# tuya-jailbeaker.net
KiCad netlist of a schematic drawn in EAGLE
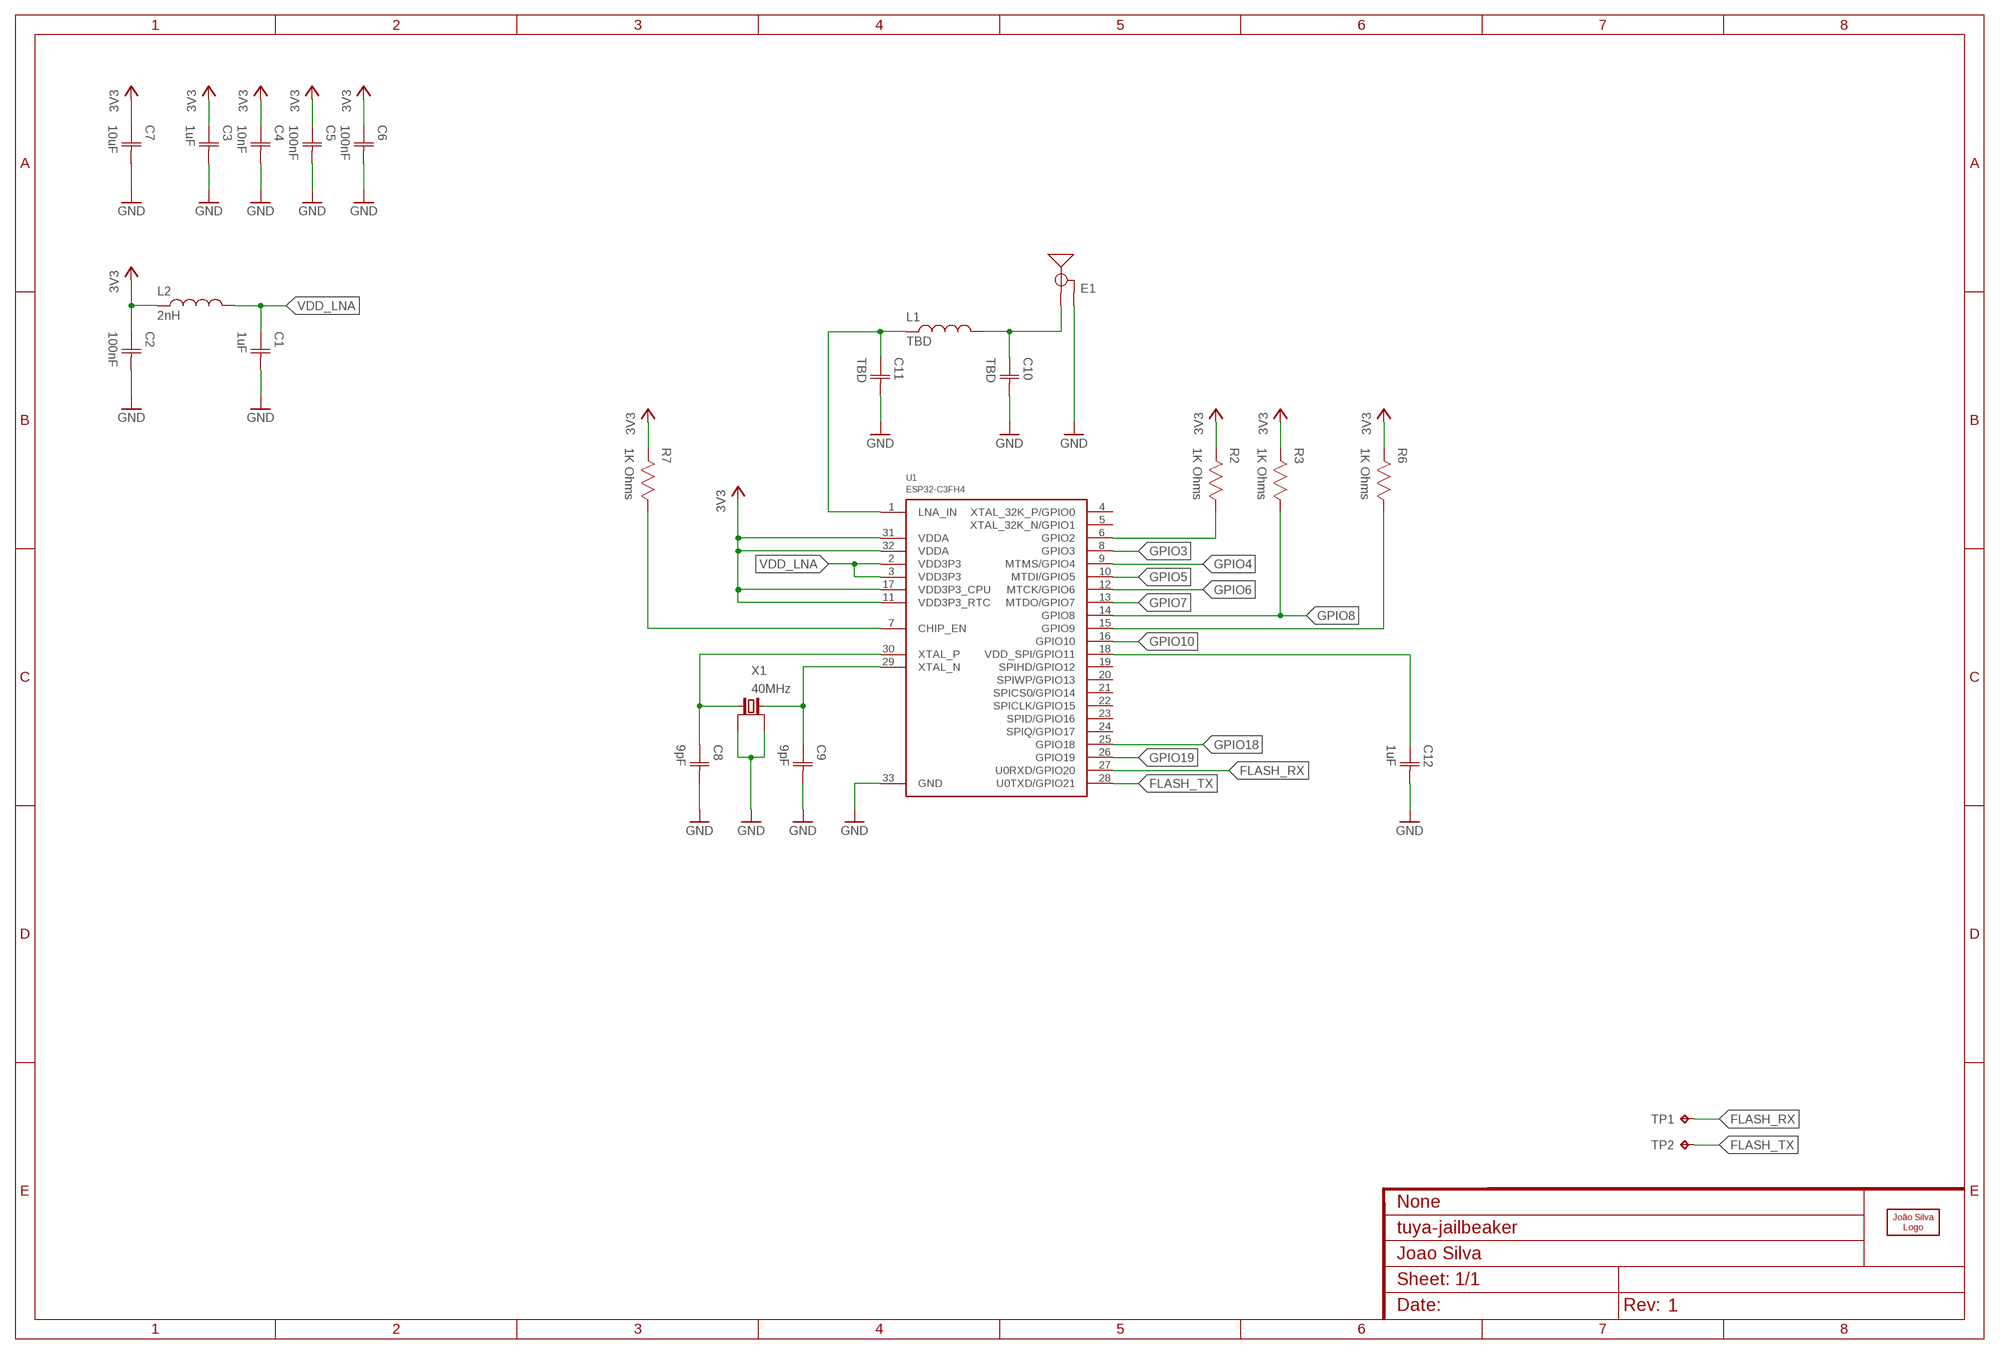
[diagram p0: schematic, sheet 1]

(export (version "E")
  (design (tool "Eeschema 10.0.6"))
  (components
    (comp (ref "C1")
      (value "1uF")
      (footprint "eagle-import:CAP0402")
      (libsource (lib "eagle-import") (part "CAPACITOR-0402"))
    )
    (comp (ref "C2")
      (value "100nF")
      (footprint "eagle-import:CAP0402")
      (libsource (lib "eagle-import") (part "CAPACITOR-0402"))
    )
    (comp (ref "C3")
      (value "1uF")
      (footprint "eagle-import:CAP0402")
      (libsource (lib "eagle-import") (part "CAPACITOR-0402"))
    )
    (comp (ref "C4")
      (value "10nF")
      (footprint "eagle-import:CAP0402")
      (libsource (lib "eagle-import") (part "CAPACITOR-0402"))
    )
    (comp (ref "C5")
      (value "100nF")
      (footprint "eagle-import:CAP0402")
      (libsource (lib "eagle-import") (part "CAPACITOR-0402"))
    )
    (comp (ref "C6")
      (value "100nF")
      (footprint "eagle-import:CAP0402")
      (libsource (lib "eagle-import") (part "CAPACITOR-0402"))
    )
    (comp (ref "C7")
      (value "10uF")
      (footprint "eagle-import:CAP0603")
      (libsource (lib "eagle-import") (part "CAPACITOR-0603"))
    )
    (comp (ref "C8")
      (value "9pF")
      (footprint "eagle-import:CAP0402")
      (libsource (lib "eagle-import") (part "CAPACITOR-0402"))
    )
    (comp (ref "C9")
      (value "9pF")
      (footprint "eagle-import:CAP0402")
      (libsource (lib "eagle-import") (part "CAPACITOR-0402"))
    )
    (comp (ref "C10")
      (value "TBD")
      (footprint "eagle-import:CAP0402")
      (libsource (lib "eagle-import") (part "CAPACITOR-0402"))
    )
    (comp (ref "C11")
      (value "TBD")
      (footprint "eagle-import:CAP0402")
      (libsource (lib "eagle-import") (part "CAPACITOR-0402"))
    )
    (comp (ref "C12")
      (value "1uF")
      (footprint "eagle-import:CAP0402")
      (libsource (lib "eagle-import") (part "CAPACITOR-0402"))
    )
    (comp (ref "E1")
      (value "2.4GHZ")
      (footprint "eagle-import:OLIMEX_ANT_ESP8266_ANT")
      (libsource (lib "eagle-import") (part "2.4GHZ"))
    )
    (comp (ref "L1")
      (value "TBD")
      (footprint "eagle-import:IND0402")
      (libsource (lib "eagle-import") (part "INDUCTOR-0402"))
    )
    (comp (ref "L2")
      (value "2nH")
      (footprint "eagle-import:IND0402")
      (libsource (lib "eagle-import") (part "INDUCTOR-0402"))
    )
    (comp (ref "LOGO1")
      (value "JS-5MM")
      (footprint "eagle-import:JS_5MM")
      (libsource (lib "eagle-import") (part "JS-5MM"))
    )
    (comp (ref "R2")
      (value "1K Ohms")
      (footprint "eagle-import:RES0402")
      (libsource (lib "eagle-import") (part "RESISTOR-0402"))
    )
    (comp (ref "R3")
      (value "1K Ohms")
      (footprint "eagle-import:RES0402")
      (libsource (lib "eagle-import") (part "RESISTOR-0402"))
    )
    (comp (ref "R6")
      (value "1K Ohms")
      (footprint "eagle-import:RES0402")
      (libsource (lib "eagle-import") (part "RESISTOR-0402"))
    )
    (comp (ref "R7")
      (value "1K Ohms")
      (footprint "eagle-import:RES0402")
      (libsource (lib "eagle-import") (part "RESISTOR-0402"))
    )
    (comp (ref "TP1")
      (value "TESTPOINT-1.27MM")
      (footprint "eagle-import:PAD1.27MM")
      (libsource (lib "eagle-import") (part "TESTPOINT-1.27MM"))
    )
    (comp (ref "TP2")
      (value "TESTPOINT-1.27MM")
      (footprint "eagle-import:PAD1.27MM")
      (libsource (lib "eagle-import") (part "TESTPOINT-1.27MM"))
    )
    (comp (ref "U1")
      (value "ESP32-C3FH4")
      (footprint "eagle-import:QFN32")
      (libsource (lib "eagle-import") (part "ESP32-C3FH4"))
    )
    (comp (ref "X1")
      (value "40MHz")
      (footprint "eagle-import:4-SMD-2520")
      (libsource (lib "eagle-import") (part "CRYSTAL_4P-2520"))
    )
  )
  (nets
    (net (code "1") (name "3V3") (class "Default")
      (node (ref "C2") (pin "1") (pinfunction "C1_1") (pintype "passive"))
      (node (ref "C3") (pin "1") (pinfunction "C1_1") (pintype "passive"))
      (node (ref "C4") (pin "1") (pinfunction "C1_1") (pintype "passive"))
      (node (ref "C5") (pin "1") (pinfunction "C1_1") (pintype "passive"))
      (node (ref "C6") (pin "1") (pinfunction "C1_1") (pintype "passive"))
      (node (ref "C7") (pin "1") (pinfunction "C1_1") (pintype "passive"))
      (node (ref "L2") (pin "1") (pinfunction "1_1") (pintype "passive"))
      (node (ref "R2") (pin "2") (pinfunction "2_2") (pintype "passive"))
      (node (ref "R3") (pin "2") (pinfunction "2_2") (pintype "passive"))
      (node (ref "R6") (pin "2") (pinfunction "2_2") (pintype "passive"))
      (node (ref "R7") (pin "2") (pinfunction "2_2") (pintype "passive"))
      (node (ref "U1") (pin "11") (pinfunction "VDD3P3_RTC_11") (pintype "bidirectional"))
      (node (ref "U1") (pin "17") (pinfunction "VDD3P3_CPU_17") (pintype "bidirectional"))
      (node (ref "U1") (pin "31") (pinfunction "VDDA_31") (pintype "bidirectional"))
      (node (ref "U1") (pin "32") (pinfunction "VDDA_32") (pintype "bidirectional"))
    )
    (net (code "2") (name "FLASH_RX") (class "Default")
      (node (ref "TP1") (pin "TP") (pinfunction "TP_TP") (pintype "input"))
      (node (ref "U1") (pin "27") (pinfunction "U0RXD/GPIO20_27") (pintype "bidirectional"))
    )
    (net (code "3") (name "FLASH_TX") (class "Default")
      (node (ref "TP2") (pin "TP") (pinfunction "TP_TP") (pintype "input"))
      (node (ref "U1") (pin "28") (pinfunction "U0TXD/GPIO21_28") (pintype "bidirectional"))
    )
    (net (code "4") (name "GND") (class "Default")
      (node (ref "C1") (pin "2") (pinfunction "C2_2") (pintype "passive"))
      (node (ref "C10") (pin "2") (pinfunction "C2_2") (pintype "passive"))
      (node (ref "C11") (pin "2") (pinfunction "C2_2") (pintype "passive"))
      (node (ref "C12") (pin "2") (pinfunction "C2_2") (pintype "passive"))
      (node (ref "C2") (pin "2") (pinfunction "C2_2") (pintype "passive"))
      (node (ref "C3") (pin "2") (pinfunction "C2_2") (pintype "passive"))
      (node (ref "C4") (pin "2") (pinfunction "C2_2") (pintype "passive"))
      (node (ref "C5") (pin "2") (pinfunction "C2_2") (pintype "passive"))
      (node (ref "C6") (pin "2") (pinfunction "C2_2") (pintype "passive"))
      (node (ref "C7") (pin "2") (pinfunction "C2_2") (pintype "passive"))
      (node (ref "C8") (pin "2") (pinfunction "C2_2") (pintype "passive"))
      (node (ref "C9") (pin "2") (pinfunction "C2_2") (pintype "passive"))
      (node (ref "E1") (pin "GND") (pinfunction "GND_GND") (pintype "bidirectional"))
      (node (ref "U1") (pin "33") (pinfunction "GND_33") (pintype "bidirectional"))
      (node (ref "X1") (pin "2") (pinfunction "GND_2") (pintype "passive"))
      (node (ref "X1") (pin "4") (pinfunction "GND_4") (pintype "passive"))
    )
    (net (code "5") (name "GPIO3") (class "Default")
      (node (ref "U1") (pin "8") (pinfunction "GPIO3_8") (pintype "bidirectional"))
    )
    (net (code "6") (name "GPIO4") (class "Default")
      (node (ref "U1") (pin "9") (pinfunction "MTMS/GPIO4_9") (pintype "bidirectional"))
    )
    (net (code "7") (name "GPIO5") (class "Default")
      (node (ref "U1") (pin "10") (pinfunction "MTDI/GPIO5_10") (pintype "bidirectional"))
    )
    (net (code "8") (name "GPIO6") (class "Default")
      (node (ref "U1") (pin "12") (pinfunction "MTCK/GPIO6_12") (pintype "bidirectional"))
    )
    (net (code "9") (name "GPIO7") (class "Default")
      (node (ref "U1") (pin "13") (pinfunction "MTDO/GPIO7_13") (pintype "bidirectional"))
    )
    (net (code "10") (name "GPIO8") (class "Default")
      (node (ref "R3") (pin "1") (pinfunction "1_1") (pintype "passive"))
      (node (ref "U1") (pin "14") (pinfunction "GPIO8_14") (pintype "bidirectional"))
    )
    (net (code "11") (name "GPIO10") (class "Default")
      (node (ref "U1") (pin "16") (pinfunction "GPIO10_16") (pintype "bidirectional"))
    )
    (net (code "12") (name "GPIO18") (class "Default")
      (node (ref "U1") (pin "25") (pinfunction "GPIO18_25") (pintype "bidirectional"))
    )
    (net (code "13") (name "GPIO19") (class "Default")
      (node (ref "U1") (pin "26") (pinfunction "GPIO19_26") (pintype "bidirectional"))
    )
    (net (code "14") (name "Net-(C8-C1)") (class "Default")
      (node (ref "C8") (pin "1") (pinfunction "C1_1") (pintype "passive"))
      (node (ref "U1") (pin "30") (pinfunction "XTAL_P_30") (pintype "bidirectional"))
      (node (ref "X1") (pin "3") (pinfunction "1_3") (pintype "passive"))
    )
    (net (code "15") (name "Net-(C9-C1)") (class "Default")
      (node (ref "C9") (pin "1") (pinfunction "C1_1") (pintype "passive"))
      (node (ref "U1") (pin "29") (pinfunction "XTAL_N_29") (pintype "bidirectional"))
      (node (ref "X1") (pin "1") (pinfunction "2_1") (pintype "passive"))
    )
    (net (code "16") (name "Net-(C10-C1)") (class "Default")
      (node (ref "C10") (pin "1") (pinfunction "C1_1") (pintype "passive"))
      (node (ref "E1") (pin "ANT") (pinfunction "SIGNAL_ANT") (pintype "bidirectional"))
      (node (ref "L1") (pin "2") (pinfunction "2_2") (pintype "passive"))
    )
    (net (code "17") (name "Net-(C11-C1)") (class "Default")
      (node (ref "C11") (pin "1") (pinfunction "C1_1") (pintype "passive"))
      (node (ref "L1") (pin "1") (pinfunction "1_1") (pintype "passive"))
      (node (ref "U1") (pin "1") (pinfunction "LNA_IN_1") (pintype "bidirectional"))
    )
    (net (code "18") (name "Net-(C12-C1)") (class "Default")
      (node (ref "C12") (pin "1") (pinfunction "C1_1") (pintype "passive"))
      (node (ref "U1") (pin "18") (pinfunction "VDD_SPI/GPIO11_18") (pintype "bidirectional"))
    )
    (net (code "19") (name "Net-(U1-CHIP_EN)") (class "Default")
      (node (ref "R7") (pin "1") (pinfunction "1_1") (pintype "passive"))
      (node (ref "U1") (pin "7") (pinfunction "CHIP_EN_7") (pintype "bidirectional"))
    )
    (net (code "20") (name "Net-(U1-GPIO2)") (class "Default")
      (node (ref "R2") (pin "1") (pinfunction "1_1") (pintype "passive"))
      (node (ref "U1") (pin "6") (pinfunction "GPIO2_6") (pintype "bidirectional"))
    )
    (net (code "21") (name "Net-(U1-GPIO9)") (class "Default")
      (node (ref "R6") (pin "1") (pinfunction "1_1") (pintype "passive"))
      (node (ref "U1") (pin "15") (pinfunction "GPIO9_15") (pintype "bidirectional"))
    )
    (net (code "22") (name "VDD_LNA") (class "Default")
      (node (ref "C1") (pin "1") (pinfunction "C1_1") (pintype "passive"))
      (node (ref "L2") (pin "2") (pinfunction "2_2") (pintype "passive"))
      (node (ref "U1") (pin "2") (pinfunction "VDD3P3_2") (pintype "bidirectional"))
      (node (ref "U1") (pin "3") (pinfunction "VDD3P3_3") (pintype "bidirectional"))
    )
    (net (code "23") (name "unconnected-(U1-SPICLK{slash}GPIO15-Pad22)") (class "Default")
      (node (ref "U1") (pin "22") (pinfunction "SPICLK/GPIO15_22") (pintype "bidirectional"))
    )
    (net (code "24") (name "unconnected-(U1-SPICS0{slash}GPIO14-Pad21)") (class "Default")
      (node (ref "U1") (pin "21") (pinfunction "SPICS0/GPIO14_21") (pintype "bidirectional"))
    )
    (net (code "25") (name "unconnected-(U1-SPID{slash}GPIO16-Pad23)") (class "Default")
      (node (ref "U1") (pin "23") (pinfunction "SPID/GPIO16_23") (pintype "bidirectional"))
    )
    (net (code "26") (name "unconnected-(U1-SPIHD{slash}GPIO12-Pad19)") (class "Default")
      (node (ref "U1") (pin "19") (pinfunction "SPIHD/GPIO12_19") (pintype "bidirectional"))
    )
    (net (code "27") (name "unconnected-(U1-SPIQ{slash}GPIO17-Pad24)") (class "Default")
      (node (ref "U1") (pin "24") (pinfunction "SPIQ/GPIO17_24") (pintype "bidirectional"))
    )
    (net (code "28") (name "unconnected-(U1-SPIWP{slash}GPIO13-Pad20)") (class "Default")
      (node (ref "U1") (pin "20") (pinfunction "SPIWP/GPIO13_20") (pintype "bidirectional"))
    )
    (net (code "29") (name "unconnected-(U1-XTAL_32K_N{slash}GPIO1-Pad5)") (class "Default")
      (node (ref "U1") (pin "5") (pinfunction "XTAL_32K_N/GPIO1_5") (pintype "bidirectional"))
    )
    (net (code "30") (name "unconnected-(U1-XTAL_32K_P{slash}GPIO0-Pad4)") (class "Default")
      (node (ref "U1") (pin "4") (pinfunction "XTAL_32K_P/GPIO0_4") (pintype "bidirectional"))
    )
  )
)
